# PWR.net
KiCad netlist of a schematic drawn in Altium Designer
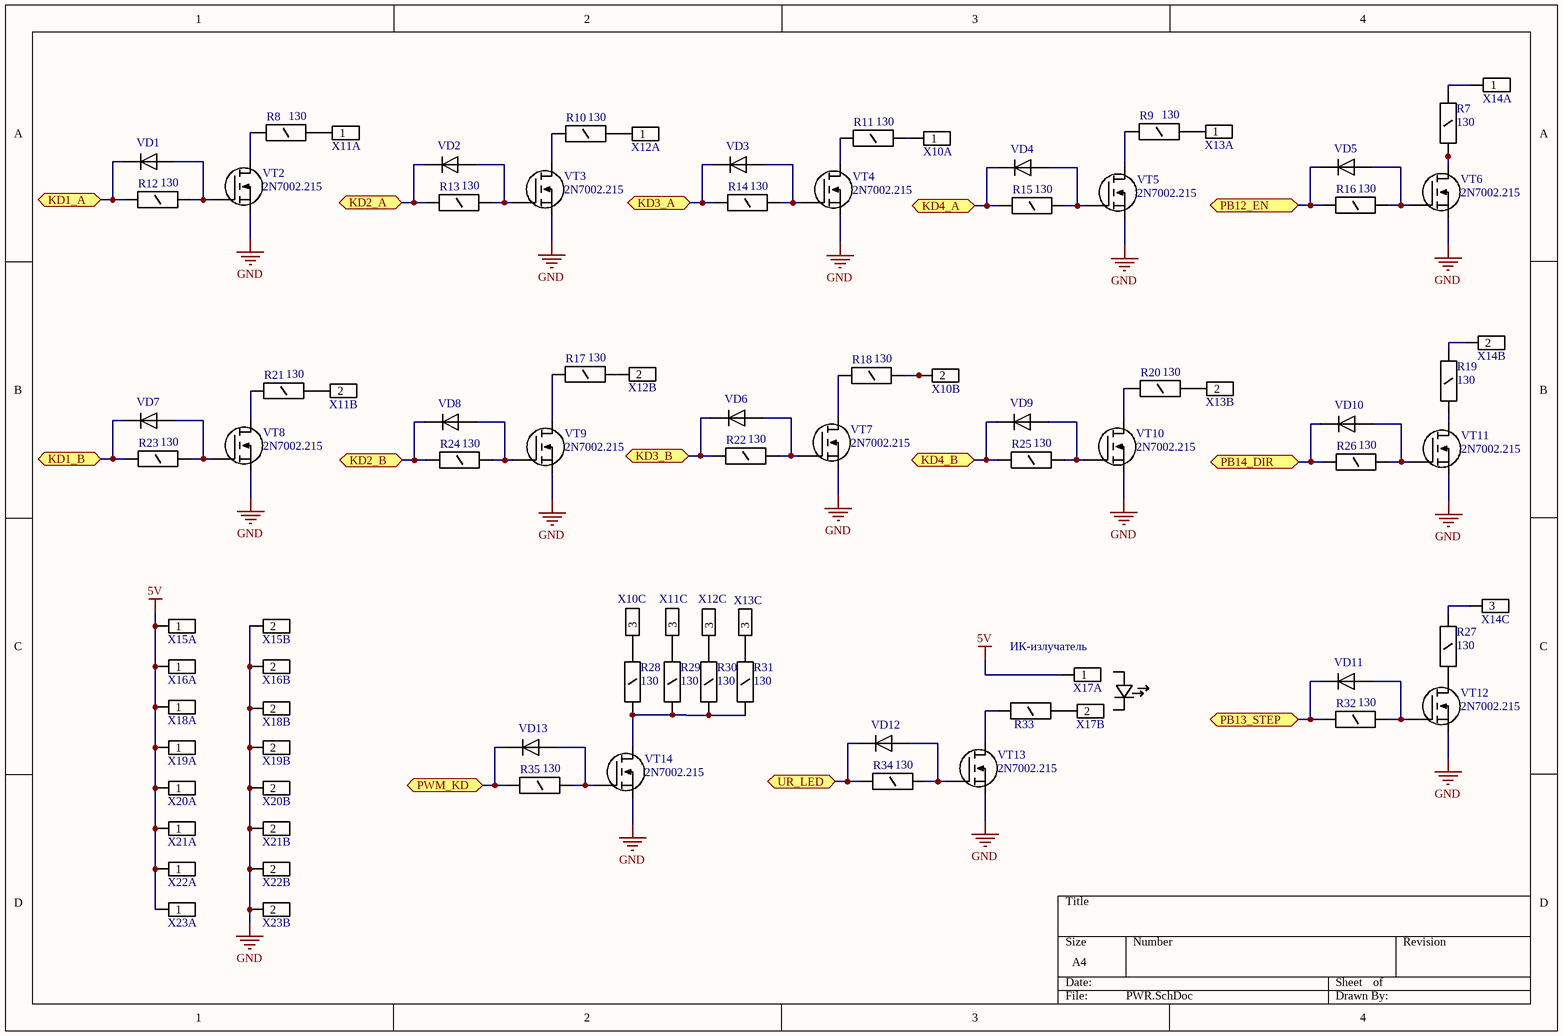
[diagram p0: PWR.SchDoc]

(export (version "E")
  (design (tool "Eeschema 10.0.6"))
  (components
    (comp (ref "R7")
      (value "130")
      (footprint "R_1206")
      (description "0,25 Вт")
      (fields (field (name "POWER") "0.25 Вт") (field (name "TOLERANCE") "5%"))
      (libsource (lib "") (part "Резистор 1206_1"))
    )
    (comp (ref "R8")
      (value "130")
      (footprint "R_1206")
      (description "0,25 Вт")
      (fields (field (name "POWER") "0.25 Вт") (field (name "TOLERANCE") "5%"))
      (libsource (lib "Res_end_Cap") (part "Резистор 1206"))
    )
    (comp (ref "R9")
      (value "130")
      (footprint "R_1206")
      (description "0,25 Вт")
      (fields (field (name "POWER") "0.25 Вт") (field (name "TOLERANCE") "5%"))
      (libsource (lib "Res_end_Cap") (part "Резистор 1206"))
    )
    (comp (ref "R10")
      (value "130")
      (footprint "R_1206")
      (description "0,25 Вт")
      (fields (field (name "POWER") "0.25 Вт") (field (name "TOLERANCE") "5%"))
      (libsource (lib "Res_end_Cap") (part "Резистор 1206"))
    )
    (comp (ref "R11")
      (value "130")
      (footprint "R_1206")
      (description "0,25 Вт")
      (fields (field (name "POWER") "0.25 Вт") (field (name "TOLERANCE") "5%"))
      (libsource (lib "Res_end_Cap") (part "Резистор 1206"))
    )
    (comp (ref "R12")
      (value "130")
      (footprint "R_1206")
      (description "0,25 Вт")
      (fields (field (name "POWER") "0.25 Вт") (field (name "TOLERANCE") "5%"))
      (libsource (lib "Res_end_Cap") (part "Резистор 1206"))
    )
    (comp (ref "R13")
      (value "130")
      (footprint "R_1206")
      (description "0,25 Вт")
      (fields (field (name "POWER") "0.25 Вт") (field (name "TOLERANCE") "5%"))
      (libsource (lib "Res_end_Cap") (part "Резистор 1206"))
    )
    (comp (ref "R14")
      (value "130")
      (footprint "R_1206")
      (description "0,25 Вт")
      (fields (field (name "POWER") "0.25 Вт") (field (name "TOLERANCE") "5%"))
      (libsource (lib "Res_end_Cap") (part "Резистор 1206"))
    )
    (comp (ref "R15")
      (value "130")
      (footprint "R_1206")
      (description "0,25 Вт")
      (fields (field (name "POWER") "0.25 Вт") (field (name "TOLERANCE") "5%"))
      (libsource (lib "Res_end_Cap") (part "Резистор 1206"))
    )
    (comp (ref "R16")
      (value "130")
      (footprint "R_1206")
      (description "0,25 Вт")
      (fields (field (name "POWER") "0.25 Вт") (field (name "TOLERANCE") "5%"))
      (libsource (lib "Res_end_Cap") (part "Резистор 1206"))
    )
    (comp (ref "R17")
      (value "130")
      (footprint "R_1206")
      (description "0,25 Вт")
      (fields (field (name "POWER") "0.25 Вт") (field (name "TOLERANCE") "5%"))
      (libsource (lib "Res_end_Cap") (part "Резистор 1206"))
    )
    (comp (ref "R18")
      (value "130")
      (footprint "R_1206")
      (description "0,25 Вт")
      (fields (field (name "POWER") "0.25 Вт") (field (name "TOLERANCE") "5%"))
      (libsource (lib "Res_end_Cap") (part "Резистор 1206"))
    )
    (comp (ref "R19")
      (value "130")
      (footprint "R_1206")
      (description "0,25 Вт")
      (fields (field (name "POWER") "0.25 Вт") (field (name "TOLERANCE") "5%"))
      (libsource (lib "") (part "Резистор 1206_1"))
    )
    (comp (ref "R20")
      (value "130")
      (footprint "R_1206")
      (description "0,25 Вт")
      (fields (field (name "POWER") "0.25 Вт") (field (name "TOLERANCE") "5%"))
      (libsource (lib "Res_end_Cap") (part "Резистор 1206"))
    )
    (comp (ref "R21")
      (value "130")
      (footprint "R_1206")
      (description "0,25 Вт")
      (fields (field (name "POWER") "0.25 Вт") (field (name "TOLERANCE") "5%"))
      (libsource (lib "Res_end_Cap") (part "Резистор 1206"))
    )
    (comp (ref "R22")
      (value "130")
      (footprint "R_1206")
      (description "0,25 Вт")
      (fields (field (name "POWER") "0.25 Вт") (field (name "TOLERANCE") "5%"))
      (libsource (lib "Res_end_Cap") (part "Резистор 1206"))
    )
    (comp (ref "R23")
      (value "130")
      (footprint "R_1206")
      (description "0,25 Вт")
      (fields (field (name "POWER") "0.25 Вт") (field (name "TOLERANCE") "5%"))
      (libsource (lib "Res_end_Cap") (part "Резистор 1206"))
    )
    (comp (ref "R24")
      (value "130")
      (footprint "R_1206")
      (description "0,25 Вт")
      (fields (field (name "POWER") "0.25 Вт") (field (name "TOLERANCE") "5%"))
      (libsource (lib "Res_end_Cap") (part "Резистор 1206"))
    )
    (comp (ref "R25")
      (value "130")
      (footprint "R_1206")
      (description "0,25 Вт")
      (fields (field (name "POWER") "0.25 Вт") (field (name "TOLERANCE") "5%"))
      (libsource (lib "Res_end_Cap") (part "Резистор 1206"))
    )
    (comp (ref "R26")
      (value "130")
      (footprint "R_1206")
      (description "0,25 Вт")
      (fields (field (name "POWER") "0.25 Вт") (field (name "TOLERANCE") "5%"))
      (libsource (lib "Res_end_Cap") (part "Резистор 1206"))
    )
    (comp (ref "R27")
      (value "130")
      (footprint "R_1206")
      (description "0,25 Вт")
      (fields (field (name "POWER") "0.25 Вт") (field (name "TOLERANCE") "5%"))
      (libsource (lib "") (part "Резистор 1206_1"))
    )
    (comp (ref "R28")
      (value "130")
      (footprint "R_1206")
      (description "0,25 Вт")
      (fields (field (name "POWER") "0.25 Вт") (field (name "TOLERANCE") "5%"))
      (libsource (lib "") (part "Резистор 1206_1"))
    )
    (comp (ref "R29")
      (value "130")
      (footprint "R_1206")
      (description "0,25 Вт")
      (fields (field (name "POWER") "0.25 Вт") (field (name "TOLERANCE") "5%"))
      (libsource (lib "") (part "Резистор 1206_1"))
    )
    (comp (ref "R30")
      (value "130")
      (footprint "R_1206")
      (description "0,25 Вт")
      (fields (field (name "POWER") "0.25 Вт") (field (name "TOLERANCE") "5%"))
      (libsource (lib "") (part "Резистор 1206_1"))
    )
    (comp (ref "R31")
      (value "130")
      (footprint "R_1206")
      (description "0,25 Вт")
      (fields (field (name "POWER") "0.25 Вт") (field (name "TOLERANCE") "5%"))
      (libsource (lib "") (part "Резистор 1206_1"))
    )
    (comp (ref "R32")
      (value "130")
      (footprint "R_1206")
      (description "0,25 Вт")
      (fields (field (name "POWER") "0.25 Вт") (field (name "TOLERANCE") "5%"))
      (libsource (lib "Res_end_Cap") (part "Резистор 1206"))
    )
    (comp (ref "R33")
      (value "0")
      (footprint "R_1206")
      (description "0,25 Вт")
      (fields (field (name "POWER") "0.25 Вт") (field (name "TOLERANCE") "5%"))
      (libsource (lib "") (part "Резистор 1206_2"))
    )
    (comp (ref "R34")
      (value "130")
      (footprint "R_1206")
      (description "0,25 Вт")
      (fields (field (name "POWER") "0.25 Вт") (field (name "TOLERANCE") "5%"))
      (libsource (lib "Res_end_Cap") (part "Резистор 1206"))
    )
    (comp (ref "R35")
      (value "130")
      (footprint "R_1206")
      (description "0,25 Вт")
      (fields (field (name "POWER") "0.25 Вт") (field (name "TOLERANCE") "5%"))
      (libsource (lib "Res_end_Cap") (part "Резистор 1206"))
    )
    (comp (ref "VD1")
      (value "SMA400*")
      (footprint "SOD-123")
      (description "диод, SMD")
      (libsource (lib "Диоды и транзисторы") (part "SMA400*"))
    )
    (comp (ref "VD2")
      (value "SMA400*")
      (footprint "SOD-123")
      (description "диод, SMD")
      (libsource (lib "Диоды и транзисторы") (part "SMA400*"))
    )
    (comp (ref "VD3")
      (value "SMA400*")
      (footprint "SOD-123")
      (description "диод, SMD")
      (libsource (lib "Диоды и транзисторы") (part "SMA400*"))
    )
    (comp (ref "VD4")
      (value "SMA400*")
      (footprint "SOD-123")
      (description "диод, SMD")
      (libsource (lib "Диоды и транзисторы") (part "SMA400*"))
    )
    (comp (ref "VD5")
      (value "SMA400*")
      (footprint "SOD-123")
      (description "диод, SMD")
      (libsource (lib "Диоды и транзисторы") (part "SMA400*"))
    )
    (comp (ref "VD6")
      (value "SMA400*")
      (footprint "SOD-123")
      (description "диод, SMD")
      (libsource (lib "Диоды и транзисторы") (part "SMA400*"))
    )
    (comp (ref "VD7")
      (value "SMA400*")
      (footprint "SOD-123")
      (description "диод, SMD")
      (libsource (lib "Диоды и транзисторы") (part "SMA400*"))
    )
    (comp (ref "VD8")
      (value "SMA400*")
      (footprint "SOD-123")
      (description "диод, SMD")
      (libsource (lib "Диоды и транзисторы") (part "SMA400*"))
    )
    (comp (ref "VD9")
      (value "SMA400*")
      (footprint "SOD-123")
      (description "диод, SMD")
      (libsource (lib "Диоды и транзисторы") (part "SMA400*"))
    )
    (comp (ref "VD10")
      (value "SMA400*")
      (footprint "SOD-123")
      (description "диод, SMD")
      (libsource (lib "Диоды и транзисторы") (part "SMA400*"))
    )
    (comp (ref "VD11")
      (value "SMA400*")
      (footprint "SOD-123")
      (description "диод, SMD")
      (libsource (lib "Диоды и транзисторы") (part "SMA400*"))
    )
    (comp (ref "VD12")
      (value "SMA400*")
      (footprint "SOD-123")
      (description "диод, SMD")
      (libsource (lib "Диоды и транзисторы") (part "SMA400*"))
    )
    (comp (ref "VD13")
      (value "SMA400*")
      (footprint "SOD-123")
      (description "диод, SMD")
      (libsource (lib "Диоды и транзисторы") (part "SMA400*"))
    )
    (comp (ref "VT2")
      (value "2N7002.215")
      (footprint "SOT23")
      (description "MOSFET, SOT23")
      (libsource (lib "Диоды и транзисторы") (part "2N7002.215"))
    )
    (comp (ref "VT3")
      (value "2N7002.215")
      (footprint "SOT23")
      (description "MOSFET, SOT23")
      (libsource (lib "Диоды и транзисторы") (part "2N7002.215"))
    )
    (comp (ref "VT4")
      (value "2N7002.215")
      (footprint "SOT23")
      (description "MOSFET, SOT23")
      (libsource (lib "Диоды и транзисторы") (part "2N7002.215"))
    )
    (comp (ref "VT5")
      (value "2N7002.215")
      (footprint "SOT23")
      (description "MOSFET, SOT23")
      (libsource (lib "Диоды и транзисторы") (part "2N7002.215"))
    )
    (comp (ref "VT6")
      (value "2N7002.215")
      (footprint "SOT23")
      (description "MOSFET, SOT23")
      (libsource (lib "Диоды и транзисторы") (part "2N7002.215"))
    )
    (comp (ref "VT7")
      (value "2N7002.215")
      (footprint "SOT23")
      (description "MOSFET, SOT23")
      (libsource (lib "Диоды и транзисторы") (part "2N7002.215"))
    )
    (comp (ref "VT8")
      (value "2N7002.215")
      (footprint "SOT23")
      (description "MOSFET, SOT23")
      (libsource (lib "Диоды и транзисторы") (part "2N7002.215"))
    )
    (comp (ref "VT9")
      (value "2N7002.215")
      (footprint "SOT23")
      (description "MOSFET, SOT23")
      (libsource (lib "Диоды и транзисторы") (part "2N7002.215"))
    )
    (comp (ref "VT10")
      (value "2N7002.215")
      (footprint "SOT23")
      (description "MOSFET, SOT23")
      (libsource (lib "Диоды и транзисторы") (part "2N7002.215"))
    )
    (comp (ref "VT11")
      (value "2N7002.215")
      (footprint "SOT23")
      (description "MOSFET, SOT23")
      (libsource (lib "Диоды и транзисторы") (part "2N7002.215"))
    )
    (comp (ref "VT12")
      (value "2N7002.215")
      (footprint "SOT23")
      (description "MOSFET, SOT23")
      (libsource (lib "Диоды и транзисторы") (part "2N7002.215"))
    )
    (comp (ref "VT13")
      (value "2N7002.215")
      (footprint "SOT23")
      (description "MOSFET, SOT23")
      (libsource (lib "Диоды и транзисторы") (part "2N7002.215"))
    )
    (comp (ref "VT14")
      (value "2N7002.215")
      (footprint "SOT23")
      (description "MOSFET, SOT23")
      (libsource (lib "Диоды и транзисторы") (part "2N7002.215"))
    )
    (comp (ref "X10")
      (value "300-031-12")
      (footprint "300-031-12")
      (description "клеммник винтовой 3к.,5мм")
      (libsource (lib "Klemniki") (part "300-031-12"))
    )
    (comp (ref "X11")
      (value "300-031-12")
      (footprint "300-031-12")
      (description "клеммник винтовой 3к.,5мм")
      (libsource (lib "Klemniki") (part "300-031-12"))
    )
    (comp (ref "X12")
      (value "300-031-12")
      (footprint "300-031-12")
      (description "клеммник винтовой 3к.,5мм")
      (libsource (lib "Klemniki") (part "300-031-12"))
    )
    (comp (ref "X13")
      (value "300-031-12")
      (footprint "300-031-12")
      (description "клеммник винтовой 3к.,5мм")
      (libsource (lib "Klemniki") (part "300-031-12"))
    )
    (comp (ref "X14")
      (value "300-031-12")
      (footprint "300-031-12")
      (description "клеммник винтовой 3к.,5мм")
      (libsource (lib "Klemniki") (part "300-031-12"))
    )
    (comp (ref "X15")
      (value "DG508V-02")
      (footprint "DG508V-02")
      (description "клеммник винтовой 2к.,5.08мм")
      (libsource (lib "Klemniki") (part "DG508V-02"))
    )
    (comp (ref "X16")
      (value "DG508V-02")
      (footprint "DG508V-02")
      (description "клеммник винтовой 2к.,5.08мм")
      (libsource (lib "Klemniki") (part "DG508V-02"))
    )
    (comp (ref "X17")
      (value "DG508V-02")
      (footprint "DG508V-02")
      (description "клеммник винтовой 2к.,5.08мм")
      (libsource (lib "Klemniki") (part "DG508V-02"))
    )
    (comp (ref "X18")
      (value "DG508V-02")
      (footprint "DG508V-02")
      (description "клеммник винтовой 2к.,5.08мм")
      (libsource (lib "Klemniki") (part "DG508V-02"))
    )
    (comp (ref "X19")
      (value "DG508V-02")
      (footprint "DG508V-02")
      (description "клеммник винтовой 2к.,5.08мм")
      (libsource (lib "Klemniki") (part "DG508V-02"))
    )
    (comp (ref "X20")
      (value "DG508V-02")
      (footprint "DG508V-02")
      (description "клеммник винтовой 2к.,5.08мм")
      (libsource (lib "Klemniki") (part "DG508V-02"))
    )
    (comp (ref "X21")
      (value "DG508V-02")
      (footprint "DG508V-02")
      (description "клеммник винтовой 2к.,5.08мм")
      (libsource (lib "Klemniki") (part "DG508V-02"))
    )
    (comp (ref "X22")
      (value "DG508V-02")
      (footprint "DG508V-02")
      (description "клеммник винтовой 2к.,5.08мм")
      (libsource (lib "Klemniki") (part "DG508V-02"))
    )
    (comp (ref "X23")
      (value "DG508V-02")
      (footprint "DG508V-02")
      (description "клеммник винтовой 2к.,5.08мм")
      (libsource (lib "Klemniki") (part "DG508V-02"))
    )
  )
  (nets
    (net (code "1") (name "/KD1_A") (class "Default")
      (node (ref "R12") (pin "1") (pinfunction "1_1") (pintype "passive"))
      (node (ref "VD1") (pin "K") (pinfunction "K_K") (pintype "passive"))
    )
    (net (code "2") (name "/KD1_B") (class "Default")
      (node (ref "R23") (pin "1") (pinfunction "1_1") (pintype "passive"))
      (node (ref "VD7") (pin "K") (pinfunction "K_K") (pintype "passive"))
    )
    (net (code "3") (name "/KD2_A") (class "Default")
      (node (ref "R13") (pin "1") (pinfunction "1_1") (pintype "passive"))
      (node (ref "VD2") (pin "K") (pinfunction "K_K") (pintype "passive"))
    )
    (net (code "4") (name "/KD2_B") (class "Default")
      (node (ref "R24") (pin "1") (pinfunction "1_1") (pintype "passive"))
      (node (ref "VD8") (pin "K") (pinfunction "K_K") (pintype "passive"))
    )
    (net (code "5") (name "/KD3_A") (class "Default")
      (node (ref "R14") (pin "1") (pinfunction "1_1") (pintype "passive"))
      (node (ref "VD3") (pin "K") (pinfunction "K_K") (pintype "passive"))
    )
    (net (code "6") (name "/KD3_B") (class "Default")
      (node (ref "R22") (pin "1") (pinfunction "1_1") (pintype "passive"))
      (node (ref "VD6") (pin "K") (pinfunction "K_K") (pintype "passive"))
    )
    (net (code "7") (name "/KD4_A") (class "Default")
      (node (ref "R15") (pin "1") (pinfunction "1_1") (pintype "passive"))
      (node (ref "VD4") (pin "K") (pinfunction "K_K") (pintype "passive"))
    )
    (net (code "8") (name "/KD4_B") (class "Default")
      (node (ref "R25") (pin "1") (pinfunction "1_1") (pintype "passive"))
      (node (ref "VD9") (pin "K") (pinfunction "K_K") (pintype "passive"))
    )
    (net (code "9") (name "/PB12_EN") (class "Default")
      (node (ref "R16") (pin "1") (pinfunction "1_1") (pintype "passive"))
      (node (ref "VD5") (pin "K") (pinfunction "K_K") (pintype "passive"))
    )
    (net (code "10") (name "/PB13_STEP") (class "Default")
      (node (ref "R32") (pin "1") (pinfunction "1_1") (pintype "passive"))
      (node (ref "VD11") (pin "K") (pinfunction "K_K") (pintype "passive"))
    )
    (net (code "11") (name "/PB14_DIR") (class "Default")
      (node (ref "R26") (pin "1") (pinfunction "1_1") (pintype "passive"))
      (node (ref "VD10") (pin "K") (pinfunction "K_K") (pintype "passive"))
    )
    (net (code "12") (name "/PWM_KD") (class "Default")
      (node (ref "R35") (pin "1") (pinfunction "1_1") (pintype "passive"))
      (node (ref "VD13") (pin "K") (pinfunction "K_K") (pintype "passive"))
    )
    (net (code "13") (name "/UR_LED") (class "Default")
      (node (ref "R34") (pin "1") (pinfunction "1_1") (pintype "passive"))
      (node (ref "VD12") (pin "K") (pinfunction "K_K") (pintype "passive"))
    )
    (net (code "14") (name "5V") (class "Default")
      (node (ref "X15") (pin "1") (pinfunction "1_1") (pintype "passive"))
      (node (ref "X16") (pin "1") (pinfunction "1_1") (pintype "passive"))
      (node (ref "X17") (pin "1") (pinfunction "1_1") (pintype "passive"))
      (node (ref "X18") (pin "1") (pinfunction "1_1") (pintype "passive"))
      (node (ref "X19") (pin "1") (pinfunction "1_1") (pintype "passive"))
      (node (ref "X20") (pin "1") (pinfunction "1_1") (pintype "passive"))
      (node (ref "X21") (pin "1") (pinfunction "1_1") (pintype "passive"))
      (node (ref "X22") (pin "1") (pinfunction "1_1") (pintype "passive"))
      (node (ref "X23") (pin "1") (pinfunction "1_1") (pintype "passive"))
    )
    (net (code "15") (name "GND") (class "Default")
      (node (ref "VT10") (pin "2") (pinfunction "S_2") (pintype "passive"))
      (node (ref "VT11") (pin "2") (pinfunction "S_2") (pintype "passive"))
      (node (ref "VT12") (pin "2") (pinfunction "S_2") (pintype "passive"))
      (node (ref "VT13") (pin "2") (pinfunction "S_2") (pintype "passive"))
      (node (ref "VT14") (pin "2") (pinfunction "S_2") (pintype "passive"))
      (node (ref "VT2") (pin "2") (pinfunction "S_2") (pintype "passive"))
      (node (ref "VT3") (pin "2") (pinfunction "S_2") (pintype "passive"))
      (node (ref "VT4") (pin "2") (pinfunction "S_2") (pintype "passive"))
      (node (ref "VT5") (pin "2") (pinfunction "S_2") (pintype "passive"))
      (node (ref "VT6") (pin "2") (pinfunction "S_2") (pintype "passive"))
      (node (ref "VT7") (pin "2") (pinfunction "S_2") (pintype "passive"))
      (node (ref "VT8") (pin "2") (pinfunction "S_2") (pintype "passive"))
      (node (ref "VT9") (pin "2") (pinfunction "S_2") (pintype "passive"))
      (node (ref "X15") (pin "2") (pinfunction "2_2") (pintype "passive"))
      (node (ref "X16") (pin "2") (pinfunction "2_2") (pintype "passive"))
      (node (ref "X18") (pin "2") (pinfunction "2_2") (pintype "passive"))
      (node (ref "X19") (pin "2") (pinfunction "2_2") (pintype "passive"))
      (node (ref "X20") (pin "2") (pinfunction "2_2") (pintype "passive"))
      (node (ref "X21") (pin "2") (pinfunction "2_2") (pintype "passive"))
      (node (ref "X22") (pin "2") (pinfunction "2_2") (pintype "passive"))
      (node (ref "X23") (pin "2") (pinfunction "2_2") (pintype "passive"))
    )
    (net (code "16") (name "Net-(R7-Pad2)") (class "Default")
      (node (ref "R7") (pin "2") (pinfunction "2_2") (pintype "passive"))
      (node (ref "X14") (pin "1") (pinfunction "1_1") (pintype "passive"))
    )
    (net (code "17") (name "Net-(R8-Pad2)") (class "Default")
      (node (ref "R8") (pin "2") (pinfunction "2_2") (pintype "passive"))
      (node (ref "X11") (pin "1") (pinfunction "1_1") (pintype "passive"))
    )
    (net (code "18") (name "Net-(R9-Pad2)") (class "Default")
      (node (ref "R9") (pin "2") (pinfunction "2_2") (pintype "passive"))
      (node (ref "X13") (pin "1") (pinfunction "1_1") (pintype "passive"))
    )
    (net (code "19") (name "Net-(R10-Pad2)") (class "Default")
      (node (ref "R10") (pin "2") (pinfunction "2_2") (pintype "passive"))
      (node (ref "X12") (pin "1") (pinfunction "1_1") (pintype "passive"))
    )
    (net (code "20") (name "Net-(R11-Pad2)") (class "Default")
      (node (ref "R11") (pin "2") (pinfunction "2_2") (pintype "passive"))
      (node (ref "X10") (pin "1") (pinfunction "1_1") (pintype "passive"))
    )
    (net (code "21") (name "Net-(R17-Pad2)") (class "Default")
      (node (ref "R17") (pin "2") (pinfunction "2_2") (pintype "passive"))
      (node (ref "X12") (pin "2") (pinfunction "2_2") (pintype "passive"))
    )
    (net (code "22") (name "Net-(R18-Pad2)") (class "Default")
      (node (ref "R18") (pin "2") (pinfunction "2_2") (pintype "passive"))
      (node (ref "X10") (pin "2") (pinfunction "2_2") (pintype "passive"))
    )
    (net (code "23") (name "Net-(R19-Pad2)") (class "Default")
      (node (ref "R19") (pin "2") (pinfunction "2_2") (pintype "passive"))
      (node (ref "X14") (pin "2") (pinfunction "2_2") (pintype "passive"))
    )
    (net (code "24") (name "Net-(R20-Pad2)") (class "Default")
      (node (ref "R20") (pin "2") (pinfunction "2_2") (pintype "passive"))
      (node (ref "X13") (pin "2") (pinfunction "2_2") (pintype "passive"))
    )
    (net (code "25") (name "Net-(R21-Pad2)") (class "Default")
      (node (ref "R21") (pin "2") (pinfunction "2_2") (pintype "passive"))
      (node (ref "X11") (pin "2") (pinfunction "2_2") (pintype "passive"))
    )
    (net (code "26") (name "Net-(R27-Pad2)") (class "Default")
      (node (ref "R27") (pin "2") (pinfunction "2_2") (pintype "passive"))
      (node (ref "X14") (pin "3") (pinfunction "3_3") (pintype "passive"))
    )
    (net (code "27") (name "Net-(R28-Pad2)") (class "Default")
      (node (ref "R28") (pin "2") (pinfunction "2_2") (pintype "passive"))
      (node (ref "X10") (pin "3") (pinfunction "3_3") (pintype "passive"))
    )
    (net (code "28") (name "Net-(R29-Pad2)") (class "Default")
      (node (ref "R29") (pin "2") (pinfunction "2_2") (pintype "passive"))
      (node (ref "X11") (pin "3") (pinfunction "3_3") (pintype "passive"))
    )
    (net (code "29") (name "Net-(R30-Pad2)") (class "Default")
      (node (ref "R30") (pin "2") (pinfunction "2_2") (pintype "passive"))
      (node (ref "X12") (pin "3") (pinfunction "3_3") (pintype "passive"))
    )
    (net (code "30") (name "Net-(R31-Pad2)") (class "Default")
      (node (ref "R31") (pin "2") (pinfunction "2_2") (pintype "passive"))
      (node (ref "X13") (pin "3") (pinfunction "3_3") (pintype "passive"))
    )
    (net (code "31") (name "Net-(R33-Pad1)") (class "Default")
      (node (ref "R33") (pin "1") (pinfunction "1_1") (pintype "passive"))
      (node (ref "X17") (pin "2") (pinfunction "2_2") (pintype "passive"))
    )
    (net (code "32") (name "Net-(VT2-D)") (class "Default")
      (node (ref "R8") (pin "1") (pinfunction "1_1") (pintype "passive"))
      (node (ref "VT2") (pin "3") (pinfunction "D_3") (pintype "passive"))
    )
    (net (code "33") (name "Net-(VT2-G)") (class "Default")
      (node (ref "R12") (pin "2") (pinfunction "2_2") (pintype "passive"))
      (node (ref "VD1") (pin "A") (pinfunction "A_A") (pintype "passive"))
      (node (ref "VT2") (pin "1") (pinfunction "G_1") (pintype "passive"))
    )
    (net (code "34") (name "Net-(VT3-D)") (class "Default")
      (node (ref "R10") (pin "1") (pinfunction "1_1") (pintype "passive"))
      (node (ref "VT3") (pin "3") (pinfunction "D_3") (pintype "passive"))
    )
    (net (code "35") (name "Net-(VT3-G)") (class "Default")
      (node (ref "R13") (pin "2") (pinfunction "2_2") (pintype "passive"))
      (node (ref "VD2") (pin "A") (pinfunction "A_A") (pintype "passive"))
      (node (ref "VT3") (pin "1") (pinfunction "G_1") (pintype "passive"))
    )
    (net (code "36") (name "Net-(VT4-D)") (class "Default")
      (node (ref "R11") (pin "1") (pinfunction "1_1") (pintype "passive"))
      (node (ref "VT4") (pin "3") (pinfunction "D_3") (pintype "passive"))
    )
    (net (code "37") (name "Net-(VT4-G)") (class "Default")
      (node (ref "R14") (pin "2") (pinfunction "2_2") (pintype "passive"))
      (node (ref "VD3") (pin "A") (pinfunction "A_A") (pintype "passive"))
      (node (ref "VT4") (pin "1") (pinfunction "G_1") (pintype "passive"))
    )
    (net (code "38") (name "Net-(VT5-D)") (class "Default")
      (node (ref "R9") (pin "1") (pinfunction "1_1") (pintype "passive"))
      (node (ref "VT5") (pin "3") (pinfunction "D_3") (pintype "passive"))
    )
    (net (code "39") (name "Net-(VT5-G)") (class "Default")
      (node (ref "R15") (pin "2") (pinfunction "2_2") (pintype "passive"))
      (node (ref "VD4") (pin "A") (pinfunction "A_A") (pintype "passive"))
      (node (ref "VT5") (pin "1") (pinfunction "G_1") (pintype "passive"))
    )
    (net (code "40") (name "Net-(VT6-D)") (class "Default")
      (node (ref "R7") (pin "1") (pinfunction "1_1") (pintype "passive"))
      (node (ref "VT6") (pin "3") (pinfunction "D_3") (pintype "passive"))
    )
    (net (code "41") (name "Net-(VT6-G)") (class "Default")
      (node (ref "R16") (pin "2") (pinfunction "2_2") (pintype "passive"))
      (node (ref "VD5") (pin "A") (pinfunction "A_A") (pintype "passive"))
      (node (ref "VT6") (pin "1") (pinfunction "G_1") (pintype "passive"))
    )
    (net (code "42") (name "Net-(VT7-D)") (class "Default")
      (node (ref "R18") (pin "1") (pinfunction "1_1") (pintype "passive"))
      (node (ref "VT7") (pin "3") (pinfunction "D_3") (pintype "passive"))
    )
    (net (code "43") (name "Net-(VT7-G)") (class "Default")
      (node (ref "R22") (pin "2") (pinfunction "2_2") (pintype "passive"))
      (node (ref "VD6") (pin "A") (pinfunction "A_A") (pintype "passive"))
      (node (ref "VT7") (pin "1") (pinfunction "G_1") (pintype "passive"))
    )
    (net (code "44") (name "Net-(VT8-D)") (class "Default")
      (node (ref "R21") (pin "1") (pinfunction "1_1") (pintype "passive"))
      (node (ref "VT8") (pin "3") (pinfunction "D_3") (pintype "passive"))
    )
    (net (code "45") (name "Net-(VT8-G)") (class "Default")
      (node (ref "R23") (pin "2") (pinfunction "2_2") (pintype "passive"))
      (node (ref "VD7") (pin "A") (pinfunction "A_A") (pintype "passive"))
      (node (ref "VT8") (pin "1") (pinfunction "G_1") (pintype "passive"))
    )
    (net (code "46") (name "Net-(VT9-D)") (class "Default")
      (node (ref "R17") (pin "1") (pinfunction "1_1") (pintype "passive"))
      (node (ref "VT9") (pin "3") (pinfunction "D_3") (pintype "passive"))
    )
    (net (code "47") (name "Net-(VT9-G)") (class "Default")
      (node (ref "R24") (pin "2") (pinfunction "2_2") (pintype "passive"))
      (node (ref "VD8") (pin "A") (pinfunction "A_A") (pintype "passive"))
      (node (ref "VT9") (pin "1") (pinfunction "G_1") (pintype "passive"))
    )
    (net (code "48") (name "Net-(VT10-D)") (class "Default")
      (node (ref "R20") (pin "1") (pinfunction "1_1") (pintype "passive"))
      (node (ref "VT10") (pin "3") (pinfunction "D_3") (pintype "passive"))
    )
    (net (code "49") (name "Net-(VT10-G)") (class "Default")
      (node (ref "R25") (pin "2") (pinfunction "2_2") (pintype "passive"))
      (node (ref "VD9") (pin "A") (pinfunction "A_A") (pintype "passive"))
      (node (ref "VT10") (pin "1") (pinfunction "G_1") (pintype "passive"))
    )
    (net (code "50") (name "Net-(VT11-D)") (class "Default")
      (node (ref "R19") (pin "1") (pinfunction "1_1") (pintype "passive"))
      (node (ref "VT11") (pin "3") (pinfunction "D_3") (pintype "passive"))
    )
    (net (code "51") (name "Net-(VT11-G)") (class "Default")
      (node (ref "R26") (pin "2") (pinfunction "2_2") (pintype "passive"))
      (node (ref "VD10") (pin "A") (pinfunction "A_A") (pintype "passive"))
      (node (ref "VT11") (pin "1") (pinfunction "G_1") (pintype "passive"))
    )
    (net (code "52") (name "Net-(VT12-D)") (class "Default")
      (node (ref "R27") (pin "1") (pinfunction "1_1") (pintype "passive"))
      (node (ref "VT12") (pin "3") (pinfunction "D_3") (pintype "passive"))
    )
    (net (code "53") (name "Net-(VT12-G)") (class "Default")
      (node (ref "R32") (pin "2") (pinfunction "2_2") (pintype "passive"))
      (node (ref "VD11") (pin "A") (pinfunction "A_A") (pintype "passive"))
      (node (ref "VT12") (pin "1") (pinfunction "G_1") (pintype "passive"))
    )
    (net (code "54") (name "Net-(VT13-D)") (class "Default")
      (node (ref "R33") (pin "2") (pinfunction "2_2") (pintype "passive"))
      (node (ref "VT13") (pin "3") (pinfunction "D_3") (pintype "passive"))
    )
    (net (code "55") (name "Net-(VT13-G)") (class "Default")
      (node (ref "R34") (pin "2") (pinfunction "2_2") (pintype "passive"))
      (node (ref "VD12") (pin "A") (pinfunction "A_A") (pintype "passive"))
      (node (ref "VT13") (pin "1") (pinfunction "G_1") (pintype "passive"))
    )
    (net (code "56") (name "Net-(VT14-D)") (class "Default")
      (node (ref "R28") (pin "1") (pinfunction "1_1") (pintype "passive"))
      (node (ref "R29") (pin "1") (pinfunction "1_1") (pintype "passive"))
      (node (ref "R30") (pin "1") (pinfunction "1_1") (pintype "passive"))
      (node (ref "R31") (pin "1") (pinfunction "1_1") (pintype "passive"))
      (node (ref "VT14") (pin "3") (pinfunction "D_3") (pintype "passive"))
    )
    (net (code "57") (name "Net-(VT14-G)") (class "Default")
      (node (ref "R35") (pin "2") (pinfunction "2_2") (pintype "passive"))
      (node (ref "VD13") (pin "A") (pinfunction "A_A") (pintype "passive"))
      (node (ref "VT14") (pin "1") (pinfunction "G_1") (pintype "passive"))
    )
  )
)
